# VRS_V1_4.net
KiCad netlist of a schematic drawn in EAGLE
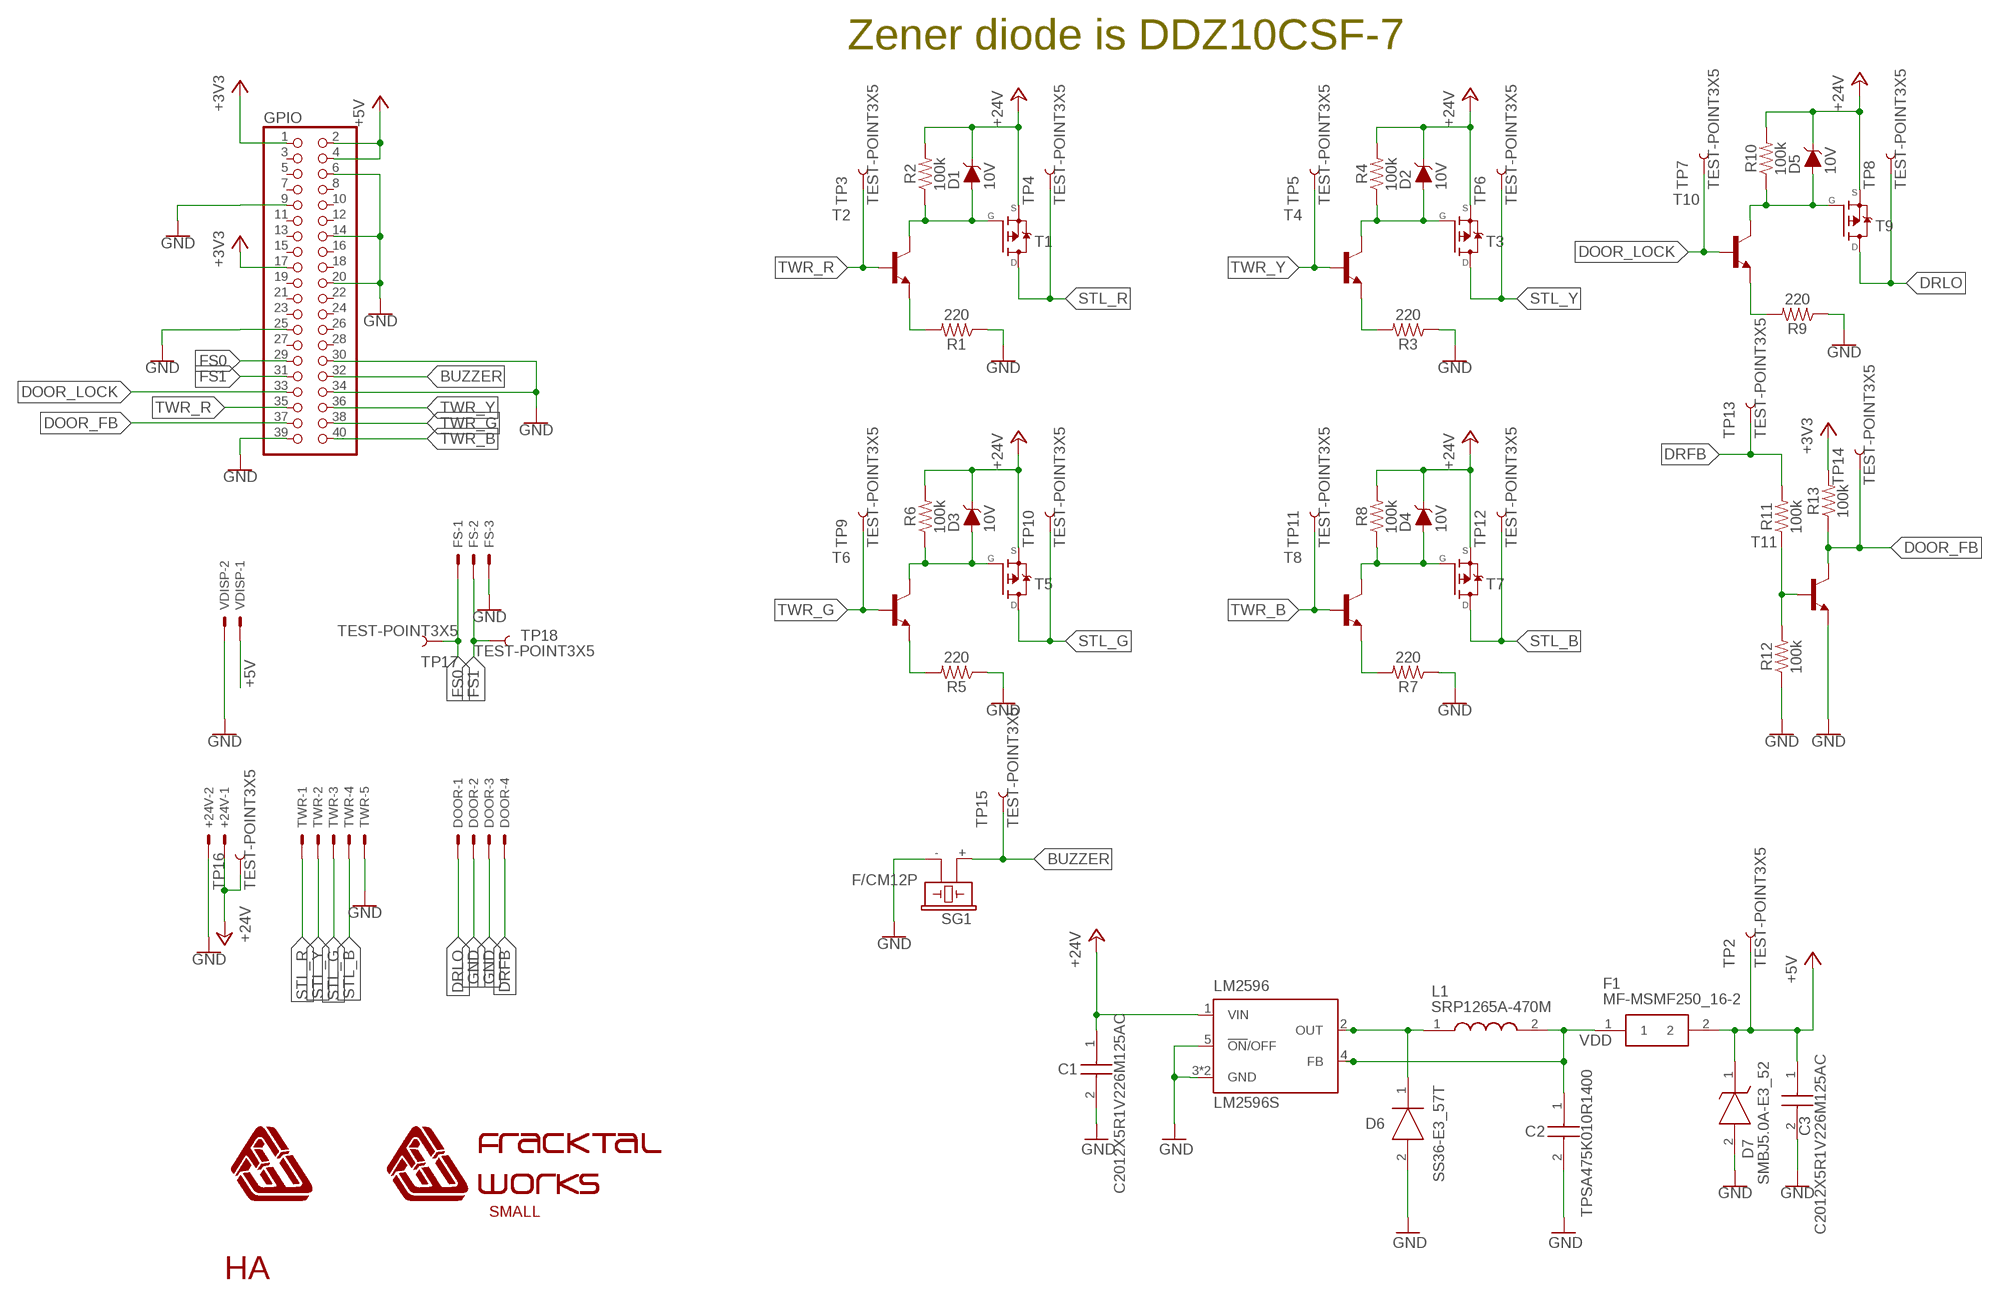
[diagram p0: schematic, sheet 1]

(export (version "E")
  (design (tool "Eeschema 10.0.6"))
  (components
    (comp (ref "+24V")
      (value "JST-XH-02-PIN-LONG-PAD")
      (footprint "eagle-import:JST-XH-02-PACKAGE-LONG-PAD")
      (libsource (lib "eagle-import") (part "JST-XH-02-PIN-LONG-PAD"))
    )
    (comp (ref "C1")
      (value "C2012X5R1V226M125AC")
      (footprint "eagle-import:CAPC2012X145N")
      (fields
        (field (name "MOUSER_PART_NUMBER") "810-C2012X5R1V226MAC")
        (field (name "RS_PART_NUMBER") "9159334P")
      )
      (libsource (lib "eagle-import") (part "C2012X5R1V226M125AC"))
    )
    (comp (ref "C2")
      (value "TPSA475K010R1400")
      (footprint "eagle-import:CAPPM3216X180N")
      (fields
        (field (name "MOUSER_PART_NUMBER") "581-TPSA475K010R1400")
        (field (name "RS_PART_NUMBER") "1366129")
      )
      (libsource (lib "eagle-import") (part "TPSA475K010R1400"))
    )
    (comp (ref "C3")
      (value "C2012X5R1V226M125AC")
      (footprint "eagle-import:CAPC2012X145N")
      (fields
        (field (name "MOUSER_PART_NUMBER") "810-C2012X5R1V226MAC")
        (field (name "RS_PART_NUMBER") "9159334P")
      )
      (libsource (lib "eagle-import") (part "C2012X5R1V226M125AC"))
    )
    (comp (ref "D1")
      (value "10V")
      (footprint "eagle-import:PANASONIC_SMINI2-F5-B")
      (libsource (lib "eagle-import") (part "DIODE-ZENER-DZ2J150M0L"))
    )
    (comp (ref "D2")
      (value "10V")
      (footprint "eagle-import:PANASONIC_SMINI2-F5-B")
      (libsource (lib "eagle-import") (part "DIODE-ZENER-DZ2J150M0L"))
    )
    (comp (ref "D3")
      (value "10V")
      (footprint "eagle-import:PANASONIC_SMINI2-F5-B")
      (libsource (lib "eagle-import") (part "DIODE-ZENER-DZ2J150M0L"))
    )
    (comp (ref "D4")
      (value "10V")
      (footprint "eagle-import:PANASONIC_SMINI2-F5-B")
      (libsource (lib "eagle-import") (part "DIODE-ZENER-DZ2J150M0L"))
    )
    (comp (ref "D5")
      (value "10V")
      (footprint "eagle-import:PANASONIC_SMINI2-F5-B")
      (libsource (lib "eagle-import") (part "DIODE-ZENER-DZ2J150M0L"))
    )
    (comp (ref "D6")
      (value "SS36-E3_57T")
      (footprint "eagle-import:DIOM7959X262N")
      (fields
        (field (name "MANUFACTURER_PART_NUMBER") "SS36-E3/57T")
        (field (name "MOUSER_PART_NUMBER") "625-SS36-E3")
        (field (name "RS_PART_NUMBER") "7000975P")
      )
      (libsource (lib "eagle-import") (part "SS36-E3_57T"))
    )
    (comp (ref "D7")
      (value "SMBJ5.0A-E3_52")
      (footprint "eagle-import:DIOM5436X244N")
      (fields
        (field (name "MANUFACTURER_PART_NUMBER") "SMBJ5.0A-E3/52")
        (field (name "MOUSER_PART_NUMBER") "625-SMBJ5.0A-E3")
        (field (name "RS_PART_NUMBER") "1652507")
      )
      (libsource (lib "eagle-import") (part "SMBJ5.0A-E3_52"))
    )
    (comp (ref "DOOR")
      (value "JST-XH-04-PIN-LONG-PAD")
      (footprint "eagle-import:JST-XH-04-PACKAGE-LONG-PAD")
      (libsource (lib "eagle-import") (part "JST-XH-04-PIN-LONG-PAD"))
    )
    (comp (ref "F1")
      (value "MF-MSMF250_16-2")
      (footprint "eagle-import:FUSC4632X160N")
      (fields
        (field (name "MANUFACTURER_PART_NUMBER") "MF-MSMF250/16-2")
        (field (name "MOUSER_PART_NUMBER") "652-MF-MSMF250/16-2")
        (field (name "RS_PART_NUMBER") "6478229P")
      )
      (libsource (lib "eagle-import") (part "MF-MSMF250_16-2"))
    )
    (comp (ref "FS")
      (value "JST-XH-03-PIN-LONG-PAD")
      (footprint "eagle-import:JST-XH-03-PACKAGE-LONG-PAD")
      (libsource (lib "eagle-import") (part "JST-XH-03-PIN-LONG-PAD"))
    )
    (comp (ref "GPIO")
      (value "RASPBERRYPI_3B_GPIO")
      (footprint "eagle-import:RASPBERRYPI_3B_GPIO")
      (libsource (lib "eagle-import") (part "RASPBERRYPI_3B_GPIO"))
    )
    (comp (ref "L1")
      (value "SRP1265A-470M")
      (footprint "eagle-import:SRP1265A")
      (fields
        (field (name "MOUSER_PART_NUMBER") "652-SRP1265A-470M")
        (field (name "RS_PART_NUMBER") "8193513P")
      )
      (libsource (lib "eagle-import") (part "SRP1265A-470M"))
    )
    (comp (ref "LM2596")
      (value "LM2596S")
      (footprint "eagle-import:LM2596_TO263-5")
      (fields (field (name "MF") "NATIONAL SEMICONDUCTOR") (field (name "MPN") "LM2596S-ADJ/NOPB"))
      (libsource (lib "eagle-import") (part "LM2596S"))
    )
    (comp (ref "M_HA_1")
      (value "HA_MARK")
      (footprint "eagle-import:HA_MARK")
      (libsource (lib "eagle-import") (part "HA_MARK"))
    )
    (comp (ref "R1")
      (value "220")
      (footprint "eagle-import:0603")
      (libsource (lib "eagle-import") (part "100KOHM-0603-1/10W-1%"))
    )
    (comp (ref "R2")
      (value "100k")
      (footprint "eagle-import:0603")
      (libsource (lib "eagle-import") (part "100KOHM-0603-1/10W-1%"))
    )
    (comp (ref "R3")
      (value "220")
      (footprint "eagle-import:0603")
      (libsource (lib "eagle-import") (part "100KOHM-0603-1/10W-1%"))
    )
    (comp (ref "R4")
      (value "100k")
      (footprint "eagle-import:0603")
      (libsource (lib "eagle-import") (part "100KOHM-0603-1/10W-1%"))
    )
    (comp (ref "R5")
      (value "220")
      (footprint "eagle-import:0603")
      (libsource (lib "eagle-import") (part "100KOHM-0603-1/10W-1%"))
    )
    (comp (ref "R6")
      (value "100k")
      (footprint "eagle-import:0603")
      (libsource (lib "eagle-import") (part "100KOHM-0603-1/10W-1%"))
    )
    (comp (ref "R7")
      (value "220")
      (footprint "eagle-import:0603")
      (libsource (lib "eagle-import") (part "100KOHM-0603-1/10W-1%"))
    )
    (comp (ref "R8")
      (value "100k")
      (footprint "eagle-import:0603")
      (libsource (lib "eagle-import") (part "100KOHM-0603-1/10W-1%"))
    )
    (comp (ref "R9")
      (value "220")
      (footprint "eagle-import:0603")
      (libsource (lib "eagle-import") (part "100KOHM-0603-1/10W-1%"))
    )
    (comp (ref "R10")
      (value "100k")
      (footprint "eagle-import:0603")
      (libsource (lib "eagle-import") (part "100KOHM-0603-1/10W-1%"))
    )
    (comp (ref "R11")
      (value "100k")
      (footprint "eagle-import:0603")
      (libsource (lib "eagle-import") (part "100KOHM-0603-1/10W-1%"))
    )
    (comp (ref "R12")
      (value "100k")
      (footprint "eagle-import:0603")
      (libsource (lib "eagle-import") (part "100KOHM-0603-1/10W-1%"))
    )
    (comp (ref "R13")
      (value "100k")
      (footprint "eagle-import:0603")
      (libsource (lib "eagle-import") (part "100KOHM-0603-1/10W-1%"))
    )
    (comp (ref "SG1")
      (value "F/CM12P")
      (footprint "eagle-import:F_CM12P")
      (libsource (lib "eagle-import") (part "F/CM12P"))
    )
    (comp (ref "T1")
      (value "MOSFET_P_SOT223")
      (footprint "eagle-import:MOSFET_SOT223")
      (libsource (lib "eagle-import") (part "MOSFET_P_SOT223"))
    )
    (comp (ref "T2")
      (value "MMBT3904LT1-NPN-SOT23-BEC")
      (footprint "eagle-import:SOT23-BEC")
      (libsource (lib "eagle-import") (part "-NPN-SOT23-BECMMBT3904LT1"))
    )
    (comp (ref "T3")
      (value "MOSFET_P_SOT223")
      (footprint "eagle-import:MOSFET_SOT223")
      (libsource (lib "eagle-import") (part "MOSFET_P_SOT223"))
    )
    (comp (ref "T4")
      (value "MMBT3904LT1-NPN-SOT23-BEC")
      (footprint "eagle-import:SOT23-BEC")
      (libsource (lib "eagle-import") (part "-NPN-SOT23-BECMMBT3904LT1"))
    )
    (comp (ref "T5")
      (value "MOSFET_P_SOT223")
      (footprint "eagle-import:MOSFET_SOT223")
      (libsource (lib "eagle-import") (part "MOSFET_P_SOT223"))
    )
    (comp (ref "T6")
      (value "MMBT3904LT1-NPN-SOT23-BEC")
      (footprint "eagle-import:SOT23-BEC")
      (libsource (lib "eagle-import") (part "-NPN-SOT23-BECMMBT3904LT1"))
    )
    (comp (ref "T7")
      (value "MOSFET_P_SOT223")
      (footprint "eagle-import:MOSFET_SOT223")
      (libsource (lib "eagle-import") (part "MOSFET_P_SOT223"))
    )
    (comp (ref "T8")
      (value "MMBT3904LT1-NPN-SOT23-BEC")
      (footprint "eagle-import:SOT23-BEC")
      (libsource (lib "eagle-import") (part "-NPN-SOT23-BECMMBT3904LT1"))
    )
    (comp (ref "T9")
      (value "MOSFET_P_SOT223")
      (footprint "eagle-import:MOSFET_SOT223")
      (libsource (lib "eagle-import") (part "MOSFET_P_SOT223"))
    )
    (comp (ref "T10")
      (value "MMBT3904LT1-NPN-SOT23-BEC")
      (footprint "eagle-import:SOT23-BEC")
      (libsource (lib "eagle-import") (part "-NPN-SOT23-BECMMBT3904LT1"))
    )
    (comp (ref "T11")
      (value "MMBT3904LT1-NPN-SOT23-BEC")
      (footprint "eagle-import:SOT23-BEC")
      (libsource (lib "eagle-import") (part "-NPN-SOT23-BECMMBT3904LT1"))
    )
    (comp (ref "TP2")
      (value "TEST-POINT3X5")
      (footprint "eagle-import:PAD.03X.05")
      (libsource (lib "eagle-import") (part "TEST-POINT3X5"))
    )
    (comp (ref "TP3")
      (value "TEST-POINT3X5")
      (footprint "eagle-import:PAD.03X.05")
      (libsource (lib "eagle-import") (part "TEST-POINT3X5"))
    )
    (comp (ref "TP4")
      (value "TEST-POINT3X5")
      (footprint "eagle-import:PAD.03X.05")
      (libsource (lib "eagle-import") (part "TEST-POINT3X5"))
    )
    (comp (ref "TP5")
      (value "TEST-POINT3X5")
      (footprint "eagle-import:PAD.03X.05")
      (libsource (lib "eagle-import") (part "TEST-POINT3X5"))
    )
    (comp (ref "TP6")
      (value "TEST-POINT3X5")
      (footprint "eagle-import:PAD.03X.05")
      (libsource (lib "eagle-import") (part "TEST-POINT3X5"))
    )
    (comp (ref "TP7")
      (value "TEST-POINT3X5")
      (footprint "eagle-import:PAD.03X.05")
      (libsource (lib "eagle-import") (part "TEST-POINT3X5"))
    )
    (comp (ref "TP8")
      (value "TEST-POINT3X5")
      (footprint "eagle-import:PAD.03X.05")
      (libsource (lib "eagle-import") (part "TEST-POINT3X5"))
    )
    (comp (ref "TP9")
      (value "TEST-POINT3X5")
      (footprint "eagle-import:PAD.03X.05")
      (libsource (lib "eagle-import") (part "TEST-POINT3X5"))
    )
    (comp (ref "TP10")
      (value "TEST-POINT3X5")
      (footprint "eagle-import:PAD.03X.05")
      (libsource (lib "eagle-import") (part "TEST-POINT3X5"))
    )
    (comp (ref "TP11")
      (value "TEST-POINT3X5")
      (footprint "eagle-import:PAD.03X.05")
      (libsource (lib "eagle-import") (part "TEST-POINT3X5"))
    )
    (comp (ref "TP12")
      (value "TEST-POINT3X5")
      (footprint "eagle-import:PAD.03X.05")
      (libsource (lib "eagle-import") (part "TEST-POINT3X5"))
    )
    (comp (ref "TP13")
      (value "TEST-POINT3X5")
      (footprint "eagle-import:PAD.03X.05")
      (libsource (lib "eagle-import") (part "TEST-POINT3X5"))
    )
    (comp (ref "TP14")
      (value "TEST-POINT3X5")
      (footprint "eagle-import:PAD.03X.05")
      (libsource (lib "eagle-import") (part "TEST-POINT3X5"))
    )
    (comp (ref "TP15")
      (value "TEST-POINT3X5")
      (footprint "eagle-import:PAD.03X.05")
      (libsource (lib "eagle-import") (part "TEST-POINT3X5"))
    )
    (comp (ref "TP16")
      (value "TEST-POINT3X5")
      (footprint "eagle-import:PAD.03X.05")
      (libsource (lib "eagle-import") (part "TEST-POINT3X5"))
    )
    (comp (ref "TP17")
      (value "TEST-POINT3X5")
      (footprint "eagle-import:PAD.03X.05")
      (libsource (lib "eagle-import") (part "TEST-POINT3X5"))
    )
    (comp (ref "TP18")
      (value "TEST-POINT3X5")
      (footprint "eagle-import:PAD.03X.05")
      (libsource (lib "eagle-import") (part "TEST-POINT3X5"))
    )
    (comp (ref "TWR")
      (value "JST-XH-05-PIN-LONG-PAD")
      (footprint "eagle-import:JST-XH-05-PACKAGE-LONG-PAD")
      (libsource (lib "eagle-import") (part "JST-XH-05-PIN-LONG-PAD"))
    )
    (comp (ref "U$1")
      (value "FWLOGO_TEXT_SMALL")
      (footprint "eagle-import:FWLOGO_TEXT_SMALL")
      (libsource (lib "eagle-import") (part "FWLOGO_TEXT_SMALL"))
    )
    (comp (ref "U$5")
      (value "FWLOGO")
      (footprint "eagle-import:FWLOGO")
      (libsource (lib "eagle-import") (part "FWLOGO"))
    )
    (comp (ref "VDISP")
      (value "JST-XH-02-PIN-LONG-PAD")
      (footprint "eagle-import:JST-XH-02-PACKAGE-LONG-PAD")
      (libsource (lib "eagle-import") (part "JST-XH-02-PIN-LONG-PAD"))
    )
  )
  (nets
    (net (code "1") (name "+3V3") (class "Default")
      (node (ref "GPIO") (pin "1") (pinfunction "1_1") (pintype "passive"))
      (node (ref "GPIO") (pin "17") (pinfunction "17_17") (pintype "passive"))
      (node (ref "R13") (pin "2") (pinfunction "2_2") (pintype "passive"))
    )
    (net (code "2") (name "+5V") (class "Default")
      (node (ref "C3") (pin "1") (pinfunction "1_1") (pintype "bidirectional"))
      (node (ref "D7") (pin "1") (pinfunction "K_1") (pintype "bidirectional"))
      (node (ref "F1") (pin "2") (pinfunction "2_2") (pintype "bidirectional"))
      (node (ref "GPIO") (pin "2") (pinfunction "2_2") (pintype "passive"))
      (node (ref "GPIO") (pin "4") (pinfunction "4_4") (pintype "passive"))
      (node (ref "TP2") (pin "P$1") (pinfunction "1_P$1") (pintype "bidirectional"))
      (node (ref "VDISP") (pin "1") (pinfunction "S_1") (pintype "passive"))
    )
    (net (code "3") (name "+24V") (class "Default")
      (node (ref "+24V") (pin "1") (pinfunction "S_1") (pintype "passive"))
      (node (ref "C1") (pin "1") (pinfunction "1_1") (pintype "bidirectional"))
      (node (ref "D1") (pin "C") (pinfunction "C_C") (pintype "passive"))
      (node (ref "D2") (pin "C") (pinfunction "C_C") (pintype "passive"))
      (node (ref "D3") (pin "C") (pinfunction "C_C") (pintype "passive"))
      (node (ref "D4") (pin "C") (pinfunction "C_C") (pintype "passive"))
      (node (ref "D5") (pin "C") (pinfunction "C_C") (pintype "passive"))
      (node (ref "LM2596") (pin "1") (pinfunction "VIN_1") (pintype "input"))
      (node (ref "R10") (pin "2") (pinfunction "2_2") (pintype "passive"))
      (node (ref "R2") (pin "2") (pinfunction "2_2") (pintype "passive"))
      (node (ref "R4") (pin "2") (pinfunction "2_2") (pintype "passive"))
      (node (ref "R6") (pin "2") (pinfunction "2_2") (pintype "passive"))
      (node (ref "R8") (pin "2") (pinfunction "2_2") (pintype "passive"))
      (node (ref "T1") (pin "3") (pinfunction "S_3") (pintype "passive"))
      (node (ref "T3") (pin "3") (pinfunction "S_3") (pintype "passive"))
      (node (ref "T5") (pin "3") (pinfunction "S_3") (pintype "passive"))
      (node (ref "T7") (pin "3") (pinfunction "S_3") (pintype "passive"))
      (node (ref "T9") (pin "3") (pinfunction "S_3") (pintype "passive"))
      (node (ref "TP16") (pin "P$1") (pinfunction "1_P$1") (pintype "bidirectional"))
    )
    (net (code "4") (name "/VDD") (class "Default")
      (node (ref "C2") (pin "1") (pinfunction "1_1") (pintype "bidirectional"))
      (node (ref "F1") (pin "1") (pinfunction "1_1") (pintype "bidirectional"))
      (node (ref "L1") (pin "2") (pinfunction "2_2") (pintype "bidirectional"))
      (node (ref "LM2596") (pin "4") (pinfunction "FB_4") (pintype "input"))
    )
    (net (code "5") (name "BUZZER") (class "Default")
      (node (ref "GPIO") (pin "32") (pinfunction "32_32") (pintype "passive"))
      (node (ref "SG1") (pin "+") (pinfunction "1_+") (pintype "passive"))
      (node (ref "TP15") (pin "P$1") (pinfunction "1_P$1") (pintype "bidirectional"))
    )
    (net (code "6") (name "DOOR_FB") (class "Default")
      (node (ref "GPIO") (pin "37") (pinfunction "37_37") (pintype "passive"))
      (node (ref "R13") (pin "1") (pinfunction "1_1") (pintype "passive"))
      (node (ref "T11") (pin "C") (pinfunction "C_C") (pintype "passive"))
      (node (ref "TP14") (pin "P$1") (pinfunction "1_P$1") (pintype "bidirectional"))
    )
    (net (code "7") (name "DOOR_LOCK") (class "Default")
      (node (ref "GPIO") (pin "33") (pinfunction "33_33") (pintype "passive"))
      (node (ref "T10") (pin "B") (pinfunction "B_B") (pintype "passive"))
      (node (ref "TP7") (pin "P$1") (pinfunction "1_P$1") (pintype "bidirectional"))
    )
    (net (code "8") (name "DRFB") (class "Default")
      (node (ref "DOOR") (pin "4") (pinfunction "S_4") (pintype "passive"))
      (node (ref "R11") (pin "2") (pinfunction "2_2") (pintype "passive"))
      (node (ref "TP13") (pin "P$1") (pinfunction "1_P$1") (pintype "bidirectional"))
    )
    (net (code "9") (name "DRLO") (class "Default")
      (node (ref "DOOR") (pin "1") (pinfunction "S_1") (pintype "passive"))
      (node (ref "T9") (pin "2") (pinfunction "D_2") (pintype "passive"))
      (node (ref "T9") (pin "4") (pinfunction "D_4") (pintype "passive"))
      (node (ref "TP8") (pin "P$1") (pinfunction "1_P$1") (pintype "bidirectional"))
    )
    (net (code "10") (name "FS0") (class "Default")
      (node (ref "FS") (pin "1") (pinfunction "S_1") (pintype "passive"))
      (node (ref "GPIO") (pin "29") (pinfunction "29_29") (pintype "passive"))
      (node (ref "TP17") (pin "P$1") (pinfunction "1_P$1") (pintype "bidirectional"))
    )
    (net (code "11") (name "FS1") (class "Default")
      (node (ref "FS") (pin "2") (pinfunction "S_2") (pintype "passive"))
      (node (ref "GPIO") (pin "31") (pinfunction "31_31") (pintype "passive"))
      (node (ref "TP18") (pin "P$1") (pinfunction "1_P$1") (pintype "bidirectional"))
    )
    (net (code "12") (name "GND") (class "Default")
      (node (ref "+24V") (pin "2") (pinfunction "S_2") (pintype "passive"))
      (node (ref "C1") (pin "2") (pinfunction "2_2") (pintype "bidirectional"))
      (node (ref "C2") (pin "2") (pinfunction "2_2") (pintype "bidirectional"))
      (node (ref "C3") (pin "2") (pinfunction "2_2") (pintype "bidirectional"))
      (node (ref "D6") (pin "2") (pinfunction "A_2") (pintype "bidirectional"))
      (node (ref "D7") (pin "2") (pinfunction "A_2") (pintype "bidirectional"))
      (node (ref "DOOR") (pin "2") (pinfunction "S_2") (pintype "passive"))
      (node (ref "DOOR") (pin "3") (pinfunction "S_3") (pintype "passive"))
      (node (ref "FS") (pin "3") (pinfunction "S_3") (pintype "passive"))
      (node (ref "GPIO") (pin "14") (pinfunction "14_14") (pintype "passive"))
      (node (ref "GPIO") (pin "20") (pinfunction "20_20") (pintype "passive"))
      (node (ref "GPIO") (pin "25") (pinfunction "25_25") (pintype "passive"))
      (node (ref "GPIO") (pin "30") (pinfunction "30_30") (pintype "passive"))
      (node (ref "GPIO") (pin "34") (pinfunction "34_34") (pintype "passive"))
      (node (ref "GPIO") (pin "39") (pinfunction "39_39") (pintype "passive"))
      (node (ref "GPIO") (pin "6") (pinfunction "6_6") (pintype "passive"))
      (node (ref "GPIO") (pin "9") (pinfunction "9_9") (pintype "passive"))
      (node (ref "LM2596") (pin "3") (pinfunction "GND_3") (pintype "power_in"))
      (node (ref "LM2596") (pin "5") (pinfunction "~{ON}/OFF_5") (pintype "input"))
      (node (ref "LM2596") (pin "6") (pinfunction "GND_6") (pintype "power_in"))
      (node (ref "R1") (pin "1") (pinfunction "1_1") (pintype "passive"))
      (node (ref "R12") (pin "1") (pinfunction "1_1") (pintype "passive"))
      (node (ref "R3") (pin "1") (pinfunction "1_1") (pintype "passive"))
      (node (ref "R5") (pin "1") (pinfunction "1_1") (pintype "passive"))
      (node (ref "R7") (pin "1") (pinfunction "1_1") (pintype "passive"))
      (node (ref "R9") (pin "1") (pinfunction "1_1") (pintype "passive"))
      (node (ref "SG1") (pin "-") (pinfunction "2_-") (pintype "passive"))
      (node (ref "T11") (pin "E") (pinfunction "E_E") (pintype "passive"))
      (node (ref "TWR") (pin "5") (pinfunction "S_5") (pintype "passive"))
      (node (ref "VDISP") (pin "2") (pinfunction "S_2") (pintype "passive"))
    )
    (net (code "13") (name "Net-(D6-K)") (class "Default")
      (node (ref "D6") (pin "1") (pinfunction "K_1") (pintype "bidirectional"))
      (node (ref "L1") (pin "1") (pinfunction "1_1") (pintype "bidirectional"))
      (node (ref "LM2596") (pin "2") (pinfunction "OUT_2") (pintype "output"))
    )
    (net (code "14") (name "Net-(R1-Pad2)") (class "Default")
      (node (ref "R1") (pin "2") (pinfunction "2_2") (pintype "passive"))
      (node (ref "T2") (pin "E") (pinfunction "E_E") (pintype "passive"))
    )
    (net (code "15") (name "Net-(R3-Pad2)") (class "Default")
      (node (ref "R3") (pin "2") (pinfunction "2_2") (pintype "passive"))
      (node (ref "T4") (pin "E") (pinfunction "E_E") (pintype "passive"))
    )
    (net (code "16") (name "Net-(R5-Pad2)") (class "Default")
      (node (ref "R5") (pin "2") (pinfunction "2_2") (pintype "passive"))
      (node (ref "T6") (pin "E") (pinfunction "E_E") (pintype "passive"))
    )
    (net (code "17") (name "Net-(R7-Pad2)") (class "Default")
      (node (ref "R7") (pin "2") (pinfunction "2_2") (pintype "passive"))
      (node (ref "T8") (pin "E") (pinfunction "E_E") (pintype "passive"))
    )
    (net (code "18") (name "Net-(R9-Pad2)") (class "Default")
      (node (ref "R9") (pin "2") (pinfunction "2_2") (pintype "passive"))
      (node (ref "T10") (pin "E") (pinfunction "E_E") (pintype "passive"))
    )
    (net (code "19") (name "Net-(R11-Pad1)") (class "Default")
      (node (ref "R11") (pin "1") (pinfunction "1_1") (pintype "passive"))
      (node (ref "R12") (pin "2") (pinfunction "2_2") (pintype "passive"))
      (node (ref "T11") (pin "B") (pinfunction "B_B") (pintype "passive"))
    )
    (net (code "20") (name "Net-(T1-G)") (class "Default")
      (node (ref "D1") (pin "A") (pinfunction "A_A") (pintype "passive"))
      (node (ref "R2") (pin "1") (pinfunction "1_1") (pintype "passive"))
      (node (ref "T1") (pin "1") (pinfunction "G_1") (pintype "passive"))
      (node (ref "T2") (pin "C") (pinfunction "C_C") (pintype "passive"))
    )
    (net (code "21") (name "Net-(T3-G)") (class "Default")
      (node (ref "D2") (pin "A") (pinfunction "A_A") (pintype "passive"))
      (node (ref "R4") (pin "1") (pinfunction "1_1") (pintype "passive"))
      (node (ref "T3") (pin "1") (pinfunction "G_1") (pintype "passive"))
      (node (ref "T4") (pin "C") (pinfunction "C_C") (pintype "passive"))
    )
    (net (code "22") (name "Net-(T5-G)") (class "Default")
      (node (ref "D3") (pin "A") (pinfunction "A_A") (pintype "passive"))
      (node (ref "R6") (pin "1") (pinfunction "1_1") (pintype "passive"))
      (node (ref "T5") (pin "1") (pinfunction "G_1") (pintype "passive"))
      (node (ref "T6") (pin "C") (pinfunction "C_C") (pintype "passive"))
    )
    (net (code "23") (name "Net-(T7-G)") (class "Default")
      (node (ref "D4") (pin "A") (pinfunction "A_A") (pintype "passive"))
      (node (ref "R8") (pin "1") (pinfunction "1_1") (pintype "passive"))
      (node (ref "T7") (pin "1") (pinfunction "G_1") (pintype "passive"))
      (node (ref "T8") (pin "C") (pinfunction "C_C") (pintype "passive"))
    )
    (net (code "24") (name "Net-(T9-G)") (class "Default")
      (node (ref "D5") (pin "A") (pinfunction "A_A") (pintype "passive"))
      (node (ref "R10") (pin "1") (pinfunction "1_1") (pintype "passive"))
      (node (ref "T10") (pin "C") (pinfunction "C_C") (pintype "passive"))
      (node (ref "T9") (pin "1") (pinfunction "G_1") (pintype "passive"))
    )
    (net (code "25") (name "STL_B") (class "Default")
      (node (ref "T7") (pin "2") (pinfunction "D_2") (pintype "passive"))
      (node (ref "T7") (pin "4") (pinfunction "D_4") (pintype "passive"))
      (node (ref "TP12") (pin "P$1") (pinfunction "1_P$1") (pintype "bidirectional"))
      (node (ref "TWR") (pin "4") (pinfunction "S_4") (pintype "passive"))
    )
    (net (code "26") (name "STL_G") (class "Default")
      (node (ref "T5") (pin "2") (pinfunction "D_2") (pintype "passive"))
      (node (ref "T5") (pin "4") (pinfunction "D_4") (pintype "passive"))
      (node (ref "TP10") (pin "P$1") (pinfunction "1_P$1") (pintype "bidirectional"))
      (node (ref "TWR") (pin "3") (pinfunction "S_3") (pintype "passive"))
    )
    (net (code "27") (name "STL_R") (class "Default")
      (node (ref "T1") (pin "2") (pinfunction "D_2") (pintype "passive"))
      (node (ref "T1") (pin "4") (pinfunction "D_4") (pintype "passive"))
      (node (ref "TP4") (pin "P$1") (pinfunction "1_P$1") (pintype "bidirectional"))
      (node (ref "TWR") (pin "1") (pinfunction "S_1") (pintype "passive"))
    )
    (net (code "28") (name "STL_Y") (class "Default")
      (node (ref "T3") (pin "2") (pinfunction "D_2") (pintype "passive"))
      (node (ref "T3") (pin "4") (pinfunction "D_4") (pintype "passive"))
      (node (ref "TP6") (pin "P$1") (pinfunction "1_P$1") (pintype "bidirectional"))
      (node (ref "TWR") (pin "2") (pinfunction "S_2") (pintype "passive"))
    )
    (net (code "29") (name "TWR_B") (class "Default")
      (node (ref "GPIO") (pin "40") (pinfunction "40_40") (pintype "passive"))
      (node (ref "T8") (pin "B") (pinfunction "B_B") (pintype "passive"))
      (node (ref "TP11") (pin "P$1") (pinfunction "1_P$1") (pintype "bidirectional"))
    )
    (net (code "30") (name "TWR_G") (class "Default")
      (node (ref "GPIO") (pin "38") (pinfunction "38_38") (pintype "passive"))
      (node (ref "T6") (pin "B") (pinfunction "B_B") (pintype "passive"))
      (node (ref "TP9") (pin "P$1") (pinfunction "1_P$1") (pintype "bidirectional"))
    )
    (net (code "31") (name "TWR_R") (class "Default")
      (node (ref "GPIO") (pin "35") (pinfunction "35_35") (pintype "passive"))
      (node (ref "T2") (pin "B") (pinfunction "B_B") (pintype "passive"))
      (node (ref "TP3") (pin "P$1") (pinfunction "1_P$1") (pintype "bidirectional"))
    )
    (net (code "32") (name "TWR_Y") (class "Default")
      (node (ref "GPIO") (pin "36") (pinfunction "36_36") (pintype "passive"))
      (node (ref "T4") (pin "B") (pinfunction "B_B") (pintype "passive"))
      (node (ref "TP5") (pin "P$1") (pinfunction "1_P$1") (pintype "bidirectional"))
    )
    (net (code "33") (name "unconnected-(GPIO-Pad3)") (class "Default")
      (node (ref "GPIO") (pin "3") (pinfunction "3_3") (pintype "passive"))
    )
    (net (code "34") (name "unconnected-(GPIO-Pad5)") (class "Default")
      (node (ref "GPIO") (pin "5") (pinfunction "5_5") (pintype "passive"))
    )
    (net (code "35") (name "unconnected-(GPIO-Pad7)") (class "Default")
      (node (ref "GPIO") (pin "7") (pinfunction "7_7") (pintype "passive"))
    )
    (net (code "36") (name "unconnected-(GPIO-Pad8)") (class "Default")
      (node (ref "GPIO") (pin "8") (pinfunction "8_8") (pintype "passive"))
    )
    (net (code "37") (name "unconnected-(GPIO-Pad10)") (class "Default")
      (node (ref "GPIO") (pin "10") (pinfunction "10_10") (pintype "passive"))
    )
    (net (code "38") (name "unconnected-(GPIO-Pad11)") (class "Default")
      (node (ref "GPIO") (pin "11") (pinfunction "11_11") (pintype "passive"))
    )
    (net (code "39") (name "unconnected-(GPIO-Pad12)") (class "Default")
      (node (ref "GPIO") (pin "12") (pinfunction "12_12") (pintype "passive"))
    )
    (net (code "40") (name "unconnected-(GPIO-Pad13)") (class "Default")
      (node (ref "GPIO") (pin "13") (pinfunction "13_13") (pintype "passive"))
    )
    (net (code "41") (name "unconnected-(GPIO-Pad15)") (class "Default")
      (node (ref "GPIO") (pin "15") (pinfunction "15_15") (pintype "passive"))
    )
    (net (code "42") (name "unconnected-(GPIO-Pad16)") (class "Default")
      (node (ref "GPIO") (pin "16") (pinfunction "16_16") (pintype "passive"))
    )
    (net (code "43") (name "unconnected-(GPIO-Pad18)") (class "Default")
      (node (ref "GPIO") (pin "18") (pinfunction "18_18") (pintype "passive"))
    )
    (net (code "44") (name "unconnected-(GPIO-Pad19)") (class "Default")
      (node (ref "GPIO") (pin "19") (pinfunction "19_19") (pintype "passive"))
    )
    (net (code "45") (name "unconnected-(GPIO-Pad21)") (class "Default")
      (node (ref "GPIO") (pin "21") (pinfunction "21_21") (pintype "passive"))
    )
    (net (code "46") (name "unconnected-(GPIO-Pad22)") (class "Default")
      (node (ref "GPIO") (pin "22") (pinfunction "22_22") (pintype "passive"))
    )
    (net (code "47") (name "unconnected-(GPIO-Pad23)") (class "Default")
      (node (ref "GPIO") (pin "23") (pinfunction "23_23") (pintype "passive"))
    )
    (net (code "48") (name "unconnected-(GPIO-Pad24)") (class "Default")
      (node (ref "GPIO") (pin "24") (pinfunction "24_24") (pintype "passive"))
    )
    (net (code "49") (name "unconnected-(GPIO-Pad26)") (class "Default")
      (node (ref "GPIO") (pin "26") (pinfunction "26_26") (pintype "passive"))
    )
    (net (code "50") (name "unconnected-(GPIO-Pad27)") (class "Default")
      (node (ref "GPIO") (pin "27") (pinfunction "27_27") (pintype "passive"))
    )
    (net (code "51") (name "unconnected-(GPIO-Pad28)") (class "Default")
      (node (ref "GPIO") (pin "28") (pinfunction "28_28") (pintype "passive"))
    )
  )
)
